# EasyADC.net
KiCad netlist of a schematic drawn in EAGLE
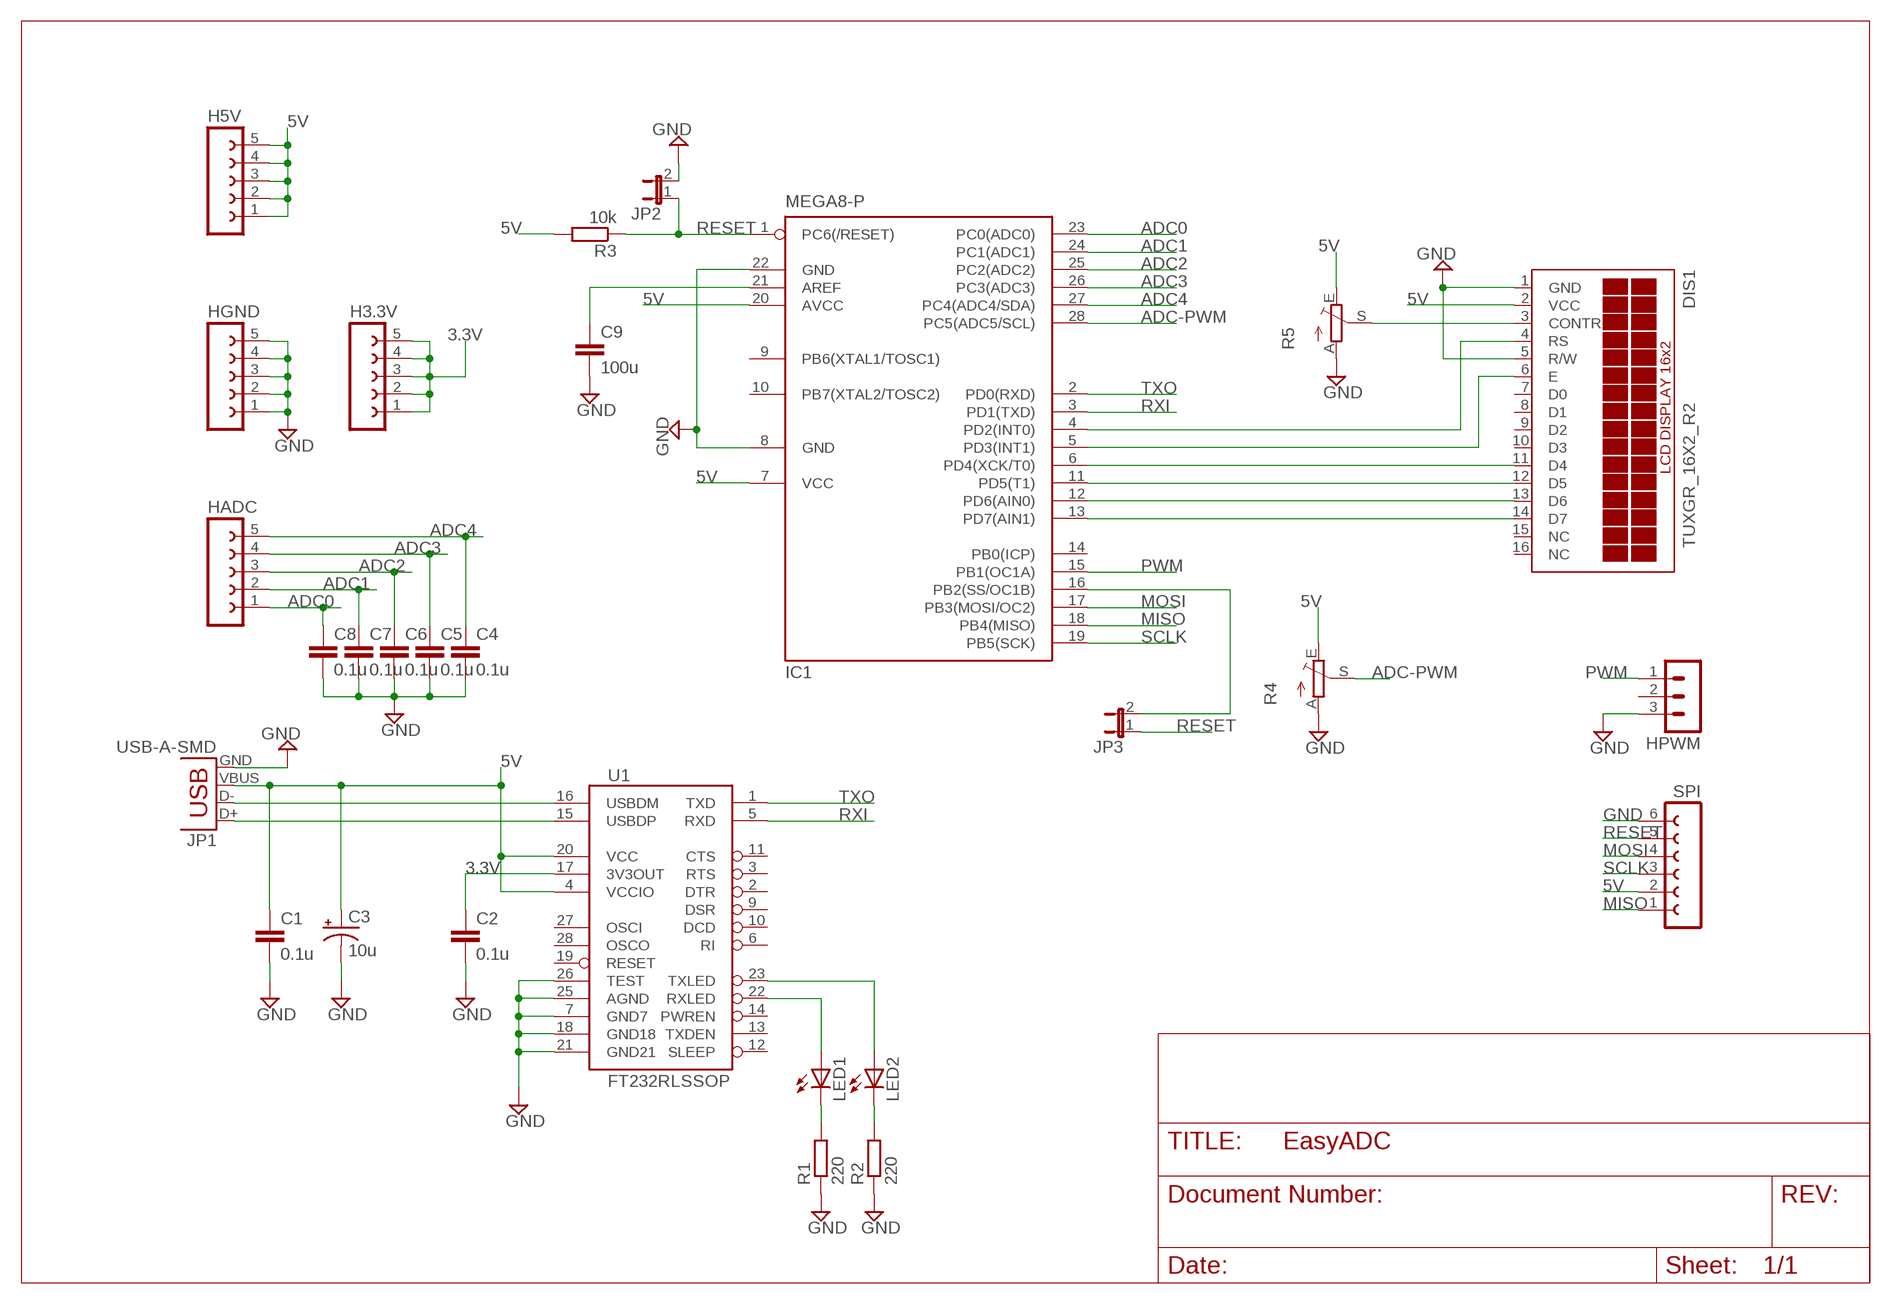
[diagram p0: schematic, sheet 1]

(export (version "E")
  (design (tool "Eeschema 10.0.6"))
  (components
    (comp (ref "C1")
      (value "0.1u")
      (footprint "eagle-import:C050-045X075")
      (libsource (lib "eagle-import") (part "C-EU050-045X075"))
    )
    (comp (ref "C2")
      (value "0.1u")
      (footprint "eagle-import:C050-045X075")
      (libsource (lib "eagle-import") (part "C-EU050-045X075"))
    )
    (comp (ref "C3")
      (value "10u")
      (footprint "eagle-import:CPOL-RADIAL-10UF-25V")
      (libsource (lib "eagle-import") (part "CAP_POLPTH2"))
    )
    (comp (ref "C4")
      (value "0.1u")
      (footprint "eagle-import:C050-045X075")
      (libsource (lib "eagle-import") (part "C-EU050-045X075"))
    )
    (comp (ref "C5")
      (value "0.1u")
      (footprint "eagle-import:C050-045X075")
      (libsource (lib "eagle-import") (part "C-EU050-045X075"))
    )
    (comp (ref "C6")
      (value "0.1u")
      (footprint "eagle-import:C050-045X075")
      (libsource (lib "eagle-import") (part "C-EU050-045X075"))
    )
    (comp (ref "C7")
      (value "0.1u")
      (footprint "eagle-import:C050-045X075")
      (libsource (lib "eagle-import") (part "C-EU050-045X075"))
    )
    (comp (ref "C8")
      (value "0.1u")
      (footprint "eagle-import:C050-045X075")
      (libsource (lib "eagle-import") (part "C-EU050-045X075"))
    )
    (comp (ref "C9")
      (value "100u")
      (footprint "eagle-import:C050-075X075")
      (libsource (lib "eagle-import") (part "C-EU050-075X075"))
    )
    (comp (ref "DIS1")
      (value "TUXGR_16X2_R2")
      (footprint "eagle-import:TUXGR_16X2_R2")
      (libsource (lib "eagle-import") (part "TUXGR_16X2_R2"))
    )
    (comp (ref "H3.3V")
      (value "FE05-1")
      (footprint "eagle-import:FE05-1")
      (libsource (lib "eagle-import") (part "FE05-1"))
    )
    (comp (ref "H5V")
      (value "FE05-1")
      (footprint "eagle-import:FE05-1")
      (libsource (lib "eagle-import") (part "FE05-1"))
    )
    (comp (ref "HADC")
      (value "FE05-1")
      (footprint "eagle-import:FE05-1")
      (libsource (lib "eagle-import") (part "FE05-1"))
    )
    (comp (ref "HGND")
      (value "FE05-1")
      (footprint "eagle-import:FE05-1")
      (libsource (lib "eagle-import") (part "FE05-1"))
    )
    (comp (ref "HPWM")
      (value "MA03-1")
      (footprint "eagle-import:MA03-1")
      (libsource (lib "eagle-import") (part "MA03-1"))
    )
    (comp (ref "IC1")
      (value "MEGA8-P")
      (footprint "eagle-import:DIL28-3")
      (libsource (lib "eagle-import") (part "MEGA8-P"))
    )
    (comp (ref "JP1")
      (value "USB-A-SMD")
      (footprint "eagle-import:USB-A-S-NOSILK-FEMALE")
      (libsource (lib "eagle-import") (part "USB-A-SMD"))
    )
    (comp (ref "JP2")
      (value "JUMPER-2PTH")
      (footprint "eagle-import:1X02")
      (libsource (lib "eagle-import") (part "JUMPER-2PTH"))
    )
    (comp (ref "JP3")
      (value "JUMPER-2PTH")
      (footprint "eagle-import:1X02")
      (libsource (lib "eagle-import") (part "JUMPER-2PTH"))
    )
    (comp (ref "LED1")
      (value "LED3MM")
      (footprint "eagle-import:LED3MM")
      (libsource (lib "eagle-import") (part "LED3MM"))
    )
    (comp (ref "LED2")
      (value "LED3MM")
      (footprint "eagle-import:LED3MM")
      (libsource (lib "eagle-import") (part "LED3MM"))
    )
    (comp (ref "R1")
      (value "220")
      (footprint "eagle-import:0207_10")
      (libsource (lib "eagle-import") (part "R-EU_0207/10"))
    )
    (comp (ref "R2")
      (value "220")
      (footprint "eagle-import:0207_10")
      (libsource (lib "eagle-import") (part "R-EU_0207/10"))
    )
    (comp (ref "R3")
      (value "10k")
      (footprint "eagle-import:0207_10")
      (libsource (lib "eagle-import") (part "R-EU_0207/10"))
    )
    (comp (ref "R4")
      (value "TRIM_EU-CA6H")
      (footprint "eagle-import:CA6H")
      (libsource (lib "eagle-import") (part "TRIM_EU-CA6H"))
    )
    (comp (ref "R5")
      (value "TRIM_EU-CA6H")
      (footprint "eagle-import:CA6H")
      (libsource (lib "eagle-import") (part "TRIM_EU-CA6H"))
    )
    (comp (ref "SPI")
      (value "FE06-1")
      (footprint "eagle-import:FE06")
      (libsource (lib "eagle-import") (part "FE06-1"))
    )
    (comp (ref "U1")
      (value "FT232RLSSOP")
      (footprint "eagle-import:SSOP28DB")
      (libsource (lib "eagle-import") (part "FT232RLSSOP"))
    )
  )
  (nets
    (net (code "1") (name "/3.3V") (class "Default")
      (node (ref "C2") (pin "1") (pinfunction "1_1") (pintype "passive"))
      (node (ref "H3.3V") (pin "1") (pinfunction "1_1") (pintype "passive"))
      (node (ref "H3.3V") (pin "2") (pinfunction "2_2") (pintype "passive"))
      (node (ref "H3.3V") (pin "3") (pinfunction "3_3") (pintype "passive"))
      (node (ref "H3.3V") (pin "4") (pinfunction "4_4") (pintype "passive"))
      (node (ref "H3.3V") (pin "5") (pinfunction "5_5") (pintype "passive"))
      (node (ref "U1") (pin "17") (pinfunction "3V3OUT_17") (pintype "output"))
    )
    (net (code "2") (name "/5V") (class "Default")
      (node (ref "C1") (pin "1") (pinfunction "1_1") (pintype "passive"))
      (node (ref "C3") (pin "1") (pinfunction "+_1") (pintype "passive"))
      (node (ref "DIS1") (pin "2") (pinfunction "VCC_2") (pintype "power_in"))
      (node (ref "H5V") (pin "1") (pinfunction "1_1") (pintype "passive"))
      (node (ref "H5V") (pin "2") (pinfunction "2_2") (pintype "passive"))
      (node (ref "H5V") (pin "3") (pinfunction "3_3") (pintype "passive"))
      (node (ref "H5V") (pin "4") (pinfunction "4_4") (pintype "passive"))
      (node (ref "H5V") (pin "5") (pinfunction "5_5") (pintype "passive"))
      (node (ref "IC1") (pin "20") (pinfunction "AVCC_20") (pintype "power_in"))
      (node (ref "IC1") (pin "7") (pinfunction "VCC_7") (pintype "power_in"))
      (node (ref "JP1") (pin "VBUS") (pinfunction "VBUS_VBUS") (pintype "bidirectional"))
      (node (ref "R3") (pin "2") (pinfunction "2_2") (pintype "passive"))
      (node (ref "R4") (pin "E") (pinfunction "E_E") (pintype "passive"))
      (node (ref "R5") (pin "E") (pinfunction "E_E") (pintype "passive"))
      (node (ref "SPI") (pin "2") (pinfunction "2_2") (pintype "passive"))
      (node (ref "U1") (pin "20") (pinfunction "VCC_20") (pintype "power_in"))
      (node (ref "U1") (pin "4") (pinfunction "VCCIO_4") (pintype "power_in"))
    )
    (net (code "3") (name "/ADC-PWM") (class "Default")
      (node (ref "IC1") (pin "28") (pinfunction "PC5(ADC5/SCL)_28") (pintype "bidirectional"))
      (node (ref "R4") (pin "S") (pinfunction "S_S") (pintype "passive"))
    )
    (net (code "4") (name "/ADC0") (class "Default")
      (node (ref "C8") (pin "1") (pinfunction "1_1") (pintype "passive"))
      (node (ref "HADC") (pin "1") (pinfunction "1_1") (pintype "passive"))
      (node (ref "IC1") (pin "23") (pinfunction "PC0(ADC0)_23") (pintype "bidirectional"))
    )
    (net (code "5") (name "/ADC1") (class "Default")
      (node (ref "C7") (pin "1") (pinfunction "1_1") (pintype "passive"))
      (node (ref "HADC") (pin "2") (pinfunction "2_2") (pintype "passive"))
      (node (ref "IC1") (pin "24") (pinfunction "PC1(ADC1)_24") (pintype "bidirectional"))
    )
    (net (code "6") (name "/ADC2") (class "Default")
      (node (ref "C6") (pin "1") (pinfunction "1_1") (pintype "passive"))
      (node (ref "HADC") (pin "3") (pinfunction "3_3") (pintype "passive"))
      (node (ref "IC1") (pin "25") (pinfunction "PC2(ADC2)_25") (pintype "bidirectional"))
    )
    (net (code "7") (name "/ADC3") (class "Default")
      (node (ref "C5") (pin "1") (pinfunction "1_1") (pintype "passive"))
      (node (ref "HADC") (pin "4") (pinfunction "4_4") (pintype "passive"))
      (node (ref "IC1") (pin "26") (pinfunction "PC3(ADC3)_26") (pintype "bidirectional"))
    )
    (net (code "8") (name "/ADC4") (class "Default")
      (node (ref "C4") (pin "1") (pinfunction "1_1") (pintype "passive"))
      (node (ref "HADC") (pin "5") (pinfunction "5_5") (pintype "passive"))
      (node (ref "IC1") (pin "27") (pinfunction "PC4(ADC4/SDA)_27") (pintype "bidirectional"))
    )
    (net (code "9") (name "/MISO") (class "Default")
      (node (ref "IC1") (pin "18") (pinfunction "PB4(MISO)_18") (pintype "bidirectional"))
      (node (ref "SPI") (pin "1") (pinfunction "1_1") (pintype "passive"))
    )
    (net (code "10") (name "/MOSI") (class "Default")
      (node (ref "IC1") (pin "17") (pinfunction "PB3(MOSI/OC2)_17") (pintype "bidirectional"))
      (node (ref "SPI") (pin "4") (pinfunction "4_4") (pintype "passive"))
    )
    (net (code "11") (name "/PWM") (class "Default")
      (node (ref "HPWM") (pin "1") (pinfunction "1_1") (pintype "passive"))
      (node (ref "IC1") (pin "15") (pinfunction "PB1(OC1A)_15") (pintype "bidirectional"))
    )
    (net (code "12") (name "/RESET") (class "Default")
      (node (ref "IC1") (pin "1") (pinfunction "PC6(/RESET)_1") (pintype "bidirectional"))
      (node (ref "JP2") (pin "1") (pinfunction "1_1") (pintype "passive"))
      (node (ref "JP3") (pin "1") (pinfunction "1_1") (pintype "passive"))
      (node (ref "R3") (pin "1") (pinfunction "1_1") (pintype "passive"))
      (node (ref "SPI") (pin "5") (pinfunction "5_5") (pintype "passive"))
    )
    (net (code "13") (name "/RXI") (class "Default")
      (node (ref "IC1") (pin "3") (pinfunction "PD1(TXD)_3") (pintype "bidirectional"))
      (node (ref "U1") (pin "5") (pinfunction "RXD_5") (pintype "input"))
    )
    (net (code "14") (name "/SCLK") (class "Default")
      (node (ref "IC1") (pin "19") (pinfunction "PB5(SCK)_19") (pintype "bidirectional"))
      (node (ref "SPI") (pin "3") (pinfunction "3_3") (pintype "passive"))
    )
    (net (code "15") (name "/TXO") (class "Default")
      (node (ref "IC1") (pin "2") (pinfunction "PD0(RXD)_2") (pintype "bidirectional"))
      (node (ref "U1") (pin "1") (pinfunction "TXD_1") (pintype "output"))
    )
    (net (code "16") (name "GND") (class "Default")
      (node (ref "C1") (pin "2") (pinfunction "2_2") (pintype "passive"))
      (node (ref "C2") (pin "2") (pinfunction "2_2") (pintype "passive"))
      (node (ref "C3") (pin "2") (pinfunction "-_2") (pintype "passive"))
      (node (ref "C4") (pin "2") (pinfunction "2_2") (pintype "passive"))
      (node (ref "C5") (pin "2") (pinfunction "2_2") (pintype "passive"))
      (node (ref "C6") (pin "2") (pinfunction "2_2") (pintype "passive"))
      (node (ref "C7") (pin "2") (pinfunction "2_2") (pintype "passive"))
      (node (ref "C8") (pin "2") (pinfunction "2_2") (pintype "passive"))
      (node (ref "C9") (pin "2") (pinfunction "2_2") (pintype "passive"))
      (node (ref "DIS1") (pin "1") (pinfunction "GND_1") (pintype "power_in"))
      (node (ref "DIS1") (pin "5") (pinfunction "R/W_5") (pintype "input"))
      (node (ref "HGND") (pin "1") (pinfunction "1_1") (pintype "passive"))
      (node (ref "HGND") (pin "2") (pinfunction "2_2") (pintype "passive"))
      (node (ref "HGND") (pin "3") (pinfunction "3_3") (pintype "passive"))
      (node (ref "HGND") (pin "4") (pinfunction "4_4") (pintype "passive"))
      (node (ref "HGND") (pin "5") (pinfunction "5_5") (pintype "passive"))
      (node (ref "HPWM") (pin "3") (pinfunction "3_3") (pintype "passive"))
      (node (ref "IC1") (pin "22") (pinfunction "GND_22") (pintype "power_in"))
      (node (ref "IC1") (pin "8") (pinfunction "GND_8") (pintype "power_in"))
      (node (ref "JP1") (pin "GND") (pinfunction "GND_GND") (pintype "bidirectional"))
      (node (ref "JP2") (pin "2") (pinfunction "2_2") (pintype "passive"))
      (node (ref "R1") (pin "1") (pinfunction "1_1") (pintype "passive"))
      (node (ref "R2") (pin "1") (pinfunction "1_1") (pintype "passive"))
      (node (ref "R4") (pin "A") (pinfunction "A_A") (pintype "passive"))
      (node (ref "R5") (pin "A") (pinfunction "A_A") (pintype "passive"))
      (node (ref "SPI") (pin "6") (pinfunction "6_6") (pintype "passive"))
      (node (ref "U1") (pin "18") (pinfunction "GND18_18") (pintype "power_in"))
      (node (ref "U1") (pin "21") (pinfunction "GND21_21") (pintype "power_in"))
      (node (ref "U1") (pin "25") (pinfunction "AGND_25") (pintype "power_in"))
      (node (ref "U1") (pin "26") (pinfunction "TEST_26") (pintype "input"))
      (node (ref "U1") (pin "7") (pinfunction "GND7_7") (pintype "power_in"))
    )
    (net (code "17") (name "Net-(DIS1-CONTR)") (class "Default")
      (node (ref "DIS1") (pin "3") (pinfunction "CONTR_3") (pintype "input"))
      (node (ref "R5") (pin "S") (pinfunction "S_S") (pintype "passive"))
    )
    (net (code "18") (name "Net-(DIS1-D4)") (class "Default")
      (node (ref "DIS1") (pin "11") (pinfunction "D4_11") (pintype "input"))
      (node (ref "IC1") (pin "6") (pinfunction "PD4(XCK/T0)_6") (pintype "bidirectional"))
    )
    (net (code "19") (name "Net-(DIS1-D5)") (class "Default")
      (node (ref "DIS1") (pin "12") (pinfunction "D5_12") (pintype "input"))
      (node (ref "IC1") (pin "11") (pinfunction "PD5(T1)_11") (pintype "bidirectional"))
    )
    (net (code "20") (name "Net-(DIS1-D6)") (class "Default")
      (node (ref "DIS1") (pin "13") (pinfunction "D6_13") (pintype "input"))
      (node (ref "IC1") (pin "12") (pinfunction "PD6(AIN0)_12") (pintype "bidirectional"))
    )
    (net (code "21") (name "Net-(DIS1-D7)") (class "Default")
      (node (ref "DIS1") (pin "14") (pinfunction "D7_14") (pintype "input"))
      (node (ref "IC1") (pin "13") (pinfunction "PD7(AIN1)_13") (pintype "bidirectional"))
    )
    (net (code "22") (name "Net-(DIS1-E)") (class "Default")
      (node (ref "DIS1") (pin "6") (pinfunction "E_6") (pintype "input"))
      (node (ref "IC1") (pin "5") (pinfunction "PD3(INT1)_5") (pintype "bidirectional"))
    )
    (net (code "23") (name "Net-(DIS1-RS)") (class "Default")
      (node (ref "DIS1") (pin "4") (pinfunction "RS_4") (pintype "input"))
      (node (ref "IC1") (pin "4") (pinfunction "PD2(INT0)_4") (pintype "bidirectional"))
    )
    (net (code "24") (name "Net-(IC1-AREF)") (class "Default")
      (node (ref "C9") (pin "1") (pinfunction "1_1") (pintype "passive"))
      (node (ref "IC1") (pin "21") (pinfunction "AREF_21") (pintype "passive"))
    )
    (net (code "25") (name "Net-(IC1-PB2(SS{slash}OC1B))") (class "Default")
      (node (ref "IC1") (pin "16") (pinfunction "PB2(SS/OC1B)_16") (pintype "bidirectional"))
      (node (ref "JP3") (pin "2") (pinfunction "2_2") (pintype "passive"))
    )
    (net (code "26") (name "Net-(LED1-C)") (class "Default")
      (node (ref "LED1") (pin "K") (pinfunction "C_K") (pintype "passive"))
      (node (ref "R1") (pin "2") (pinfunction "2_2") (pintype "passive"))
    )
    (net (code "27") (name "Net-(LED2-C)") (class "Default")
      (node (ref "LED2") (pin "K") (pinfunction "C_K") (pintype "passive"))
      (node (ref "R2") (pin "2") (pinfunction "2_2") (pintype "passive"))
    )
    (net (code "28") (name "Net-(U1-RXLED)") (class "Default")
      (node (ref "LED1") (pin "A") (pinfunction "A_A") (pintype "passive"))
      (node (ref "U1") (pin "22") (pinfunction "RXLED_22") (pintype "input"))
    )
    (net (code "29") (name "Net-(U1-TXLED)") (class "Default")
      (node (ref "LED2") (pin "A") (pinfunction "A_A") (pintype "passive"))
      (node (ref "U1") (pin "23") (pinfunction "TXLED_23") (pintype "input"))
    )
    (net (code "30") (name "Net-(U1-USBDM)") (class "Default")
      (node (ref "JP1") (pin "D-") (pinfunction "D-_D-") (pintype "bidirectional"))
      (node (ref "U1") (pin "16") (pinfunction "USBDM_16") (pintype "bidirectional"))
    )
    (net (code "31") (name "Net-(U1-USBDP)") (class "Default")
      (node (ref "JP1") (pin "D+") (pinfunction "D+_D+") (pintype "bidirectional"))
      (node (ref "U1") (pin "15") (pinfunction "USBDP_15") (pintype "bidirectional"))
    )
    (net (code "32") (name "unconnected-(DIS1-D0-Pad7)") (class "Default")
      (node (ref "DIS1") (pin "7") (pinfunction "D0_7") (pintype "input"))
    )
    (net (code "33") (name "unconnected-(DIS1-D1-Pad8)") (class "Default")
      (node (ref "DIS1") (pin "8") (pinfunction "D1_8") (pintype "input"))
    )
    (net (code "34") (name "unconnected-(DIS1-D2-Pad9)") (class "Default")
      (node (ref "DIS1") (pin "9") (pinfunction "D2_9") (pintype "input"))
    )
    (net (code "35") (name "unconnected-(DIS1-D3-Pad10)") (class "Default")
      (node (ref "DIS1") (pin "10") (pinfunction "D3_10") (pintype "input"))
    )
    (net (code "36") (name "unconnected-(DIS1-NC-Pad15)") (class "Default")
      (node (ref "DIS1") (pin "15") (pinfunction "NC_15") (pintype "no_connect"))
    )
    (net (code "37") (name "unconnected-(DIS1-NC-Pad16)") (class "Default")
      (node (ref "DIS1") (pin "16") (pinfunction "NC_16") (pintype "no_connect"))
    )
    (net (code "38") (name "unconnected-(HPWM-Pad2)") (class "Default")
      (node (ref "HPWM") (pin "2") (pinfunction "2_2") (pintype "passive"))
    )
    (net (code "39") (name "unconnected-(IC1-PB0(ICP)-Pad14)") (class "Default")
      (node (ref "IC1") (pin "14") (pinfunction "PB0(ICP)_14") (pintype "bidirectional"))
    )
    (net (code "40") (name "unconnected-(IC1-PB6(XTAL1{slash}TOSC1)-Pad9)") (class "Default")
      (node (ref "IC1") (pin "9") (pinfunction "PB6(XTAL1/TOSC1)_9") (pintype "bidirectional"))
    )
    (net (code "41") (name "unconnected-(IC1-PB7(XTAL2{slash}TOSC2)-Pad10)") (class "Default")
      (node (ref "IC1") (pin "10") (pinfunction "PB7(XTAL2/TOSC2)_10") (pintype "bidirectional"))
    )
    (net (code "42") (name "unconnected-(U1-CTS-Pad11)") (class "Default")
      (node (ref "U1") (pin "11") (pinfunction "CTS_11") (pintype "input"))
    )
    (net (code "43") (name "unconnected-(U1-DCD-Pad10)") (class "Default")
      (node (ref "U1") (pin "10") (pinfunction "DCD_10") (pintype "input"))
    )
    (net (code "44") (name "unconnected-(U1-DSR-Pad9)") (class "Default")
      (node (ref "U1") (pin "9") (pinfunction "DSR_9") (pintype "input"))
    )
    (net (code "45") (name "unconnected-(U1-DTR-Pad2)") (class "Default")
      (node (ref "U1") (pin "2") (pinfunction "DTR_2") (pintype "output"))
    )
    (net (code "46") (name "unconnected-(U1-OSCI-Pad27)") (class "Default")
      (node (ref "U1") (pin "27") (pinfunction "OSCI_27") (pintype "input"))
    )
    (net (code "47") (name "unconnected-(U1-OSCO-Pad28)") (class "Default")
      (node (ref "U1") (pin "28") (pinfunction "OSCO_28") (pintype "output"))
    )
    (net (code "48") (name "unconnected-(U1-PWREN-Pad14)") (class "Default")
      (node (ref "U1") (pin "14") (pinfunction "PWREN_14") (pintype "input"))
    )
    (net (code "49") (name "unconnected-(U1-RESET-Pad19)") (class "Default")
      (node (ref "U1") (pin "19") (pinfunction "RESET_19") (pintype "input"))
    )
    (net (code "50") (name "unconnected-(U1-RI-Pad6)") (class "Default")
      (node (ref "U1") (pin "6") (pinfunction "RI_6") (pintype "input"))
    )
    (net (code "51") (name "unconnected-(U1-RTS-Pad3)") (class "Default")
      (node (ref "U1") (pin "3") (pinfunction "RTS_3") (pintype "output"))
    )
    (net (code "52") (name "unconnected-(U1-SLEEP-Pad12)") (class "Default")
      (node (ref "U1") (pin "12") (pinfunction "SLEEP_12") (pintype "input"))
    )
    (net (code "53") (name "unconnected-(U1-TXDEN-Pad13)") (class "Default")
      (node (ref "U1") (pin "13") (pinfunction "TXDEN_13") (pintype "input"))
    )
  )
)
